# 7seg-2_54.net
KiCad netlist of a schematic drawn in EAGLE
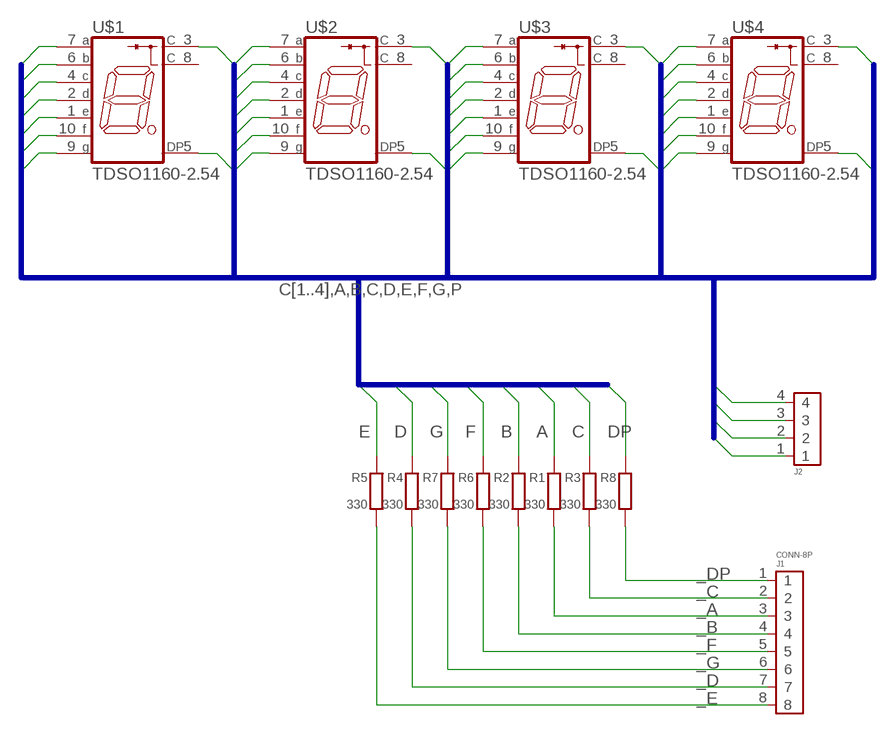
[diagram p0: schematic, sheet 1]

(export (version "E")
  (design (tool "Eeschema 10.0.6"))
  (components
    (comp (ref "J1")
      (value "CONN-8P")
      (footprint "eagle-import:CONN-8P")
      (libsource (lib "eagle-import") (part "CONN-8P"))
    )
    (comp (ref "J2")
      (value "CONN-4P-4P")
      (footprint "eagle-import:CONN-4P")
      (libsource (lib "eagle-import") (part "CONN-4P-4P"))
    )
    (comp (ref "R1")
      (value "330")
      (footprint "eagle-import:0202_5-V")
      (libsource (lib "eagle-import") (part "R0202/5-V"))
    )
    (comp (ref "R2")
      (value "330")
      (footprint "eagle-import:0202_5-V")
      (libsource (lib "eagle-import") (part "R0202/5-V"))
    )
    (comp (ref "R3")
      (value "330")
      (footprint "eagle-import:0202_5-V")
      (libsource (lib "eagle-import") (part "R0202/5-V"))
    )
    (comp (ref "R4")
      (value "330")
      (footprint "eagle-import:0202_5-V")
      (libsource (lib "eagle-import") (part "R0202/5-V"))
    )
    (comp (ref "R5")
      (value "330")
      (footprint "eagle-import:0202_5-V")
      (libsource (lib "eagle-import") (part "R0202/5-V"))
    )
    (comp (ref "R6")
      (value "330")
      (footprint "eagle-import:0202_5-V")
      (libsource (lib "eagle-import") (part "R0202/5-V"))
    )
    (comp (ref "R7")
      (value "330")
      (footprint "eagle-import:0202_5-V")
      (libsource (lib "eagle-import") (part "R0202/5-V"))
    )
    (comp (ref "R8")
      (value "330")
      (footprint "eagle-import:0202_5-V")
      (libsource (lib "eagle-import") (part "R0202/5-V"))
    )
    (comp (ref "U$1")
      (value "TDSO1160-2.54")
      (footprint "eagle-import:TDSX1150-2.54")
      (libsource (lib "eagle-import") (part "TDSO1160-2.54"))
    )
    (comp (ref "U$2")
      (value "TDSO1160-2.54")
      (footprint "eagle-import:TDSX1150-2.54")
      (libsource (lib "eagle-import") (part "TDSO1160-2.54"))
    )
    (comp (ref "U$3")
      (value "TDSO1160-2.54")
      (footprint "eagle-import:TDSX1150-2.54")
      (libsource (lib "eagle-import") (part "TDSO1160-2.54"))
    )
    (comp (ref "U$4")
      (value "TDSO1160-2.54")
      (footprint "eagle-import:TDSX1150-2.54")
      (libsource (lib "eagle-import") (part "TDSO1160-2.54"))
    )
  )
  (nets
    (net (code "2") (name "/A") (class "Default")
      (node (ref "R1") (pin "1") (pinfunction "2_1") (pintype "passive"))
      (node (ref "U$1") (pin "7") (pinfunction "A_7") (pintype "passive"))
      (node (ref "U$2") (pin "7") (pinfunction "A_7") (pintype "passive"))
      (node (ref "U$3") (pin "7") (pinfunction "A_7") (pintype "passive"))
      (node (ref "U$4") (pin "7") (pinfunction "A_7") (pintype "passive"))
    )
    (net (code "3") (name "/B") (class "Default")
      (node (ref "R2") (pin "1") (pinfunction "2_1") (pintype "passive"))
      (node (ref "U$1") (pin "6") (pinfunction "B_6") (pintype "passive"))
      (node (ref "U$2") (pin "6") (pinfunction "B_6") (pintype "passive"))
      (node (ref "U$3") (pin "6") (pinfunction "B_6") (pintype "passive"))
      (node (ref "U$4") (pin "6") (pinfunction "B_6") (pintype "passive"))
    )
    (net (code "4") (name "/C") (class "Default")
      (node (ref "R3") (pin "1") (pinfunction "2_1") (pintype "passive"))
      (node (ref "U$1") (pin "4") (pinfunction "C_4") (pintype "passive"))
      (node (ref "U$2") (pin "4") (pinfunction "C_4") (pintype "passive"))
      (node (ref "U$3") (pin "4") (pinfunction "C_4") (pintype "passive"))
      (node (ref "U$4") (pin "4") (pinfunction "C_4") (pintype "passive"))
    )
    (net (code "5") (name "/C1") (class "Default")
      (node (ref "J2") (pin "1") (pinfunction "1_1") (pintype "bidirectional"))
      (node (ref "U$1") (pin "3") (pinfunction "C_3") (pintype "passive"))
    )
    (net (code "6") (name "/C2") (class "Default")
      (node (ref "J2") (pin "2") (pinfunction "2_2") (pintype "bidirectional"))
      (node (ref "U$2") (pin "3") (pinfunction "C_3") (pintype "passive"))
    )
    (net (code "7") (name "/C3") (class "Default")
      (node (ref "J2") (pin "3") (pinfunction "3_3") (pintype "bidirectional"))
      (node (ref "U$3") (pin "3") (pinfunction "C_3") (pintype "passive"))
    )
    (net (code "8") (name "/C4") (class "Default")
      (node (ref "J2") (pin "4") (pinfunction "4_4") (pintype "bidirectional"))
      (node (ref "U$4") (pin "3") (pinfunction "C_3") (pintype "passive"))
    )
    (net (code "9") (name "/D") (class "Default")
      (node (ref "R4") (pin "1") (pinfunction "2_1") (pintype "passive"))
      (node (ref "U$1") (pin "2") (pinfunction "D_2") (pintype "passive"))
      (node (ref "U$2") (pin "2") (pinfunction "D_2") (pintype "passive"))
      (node (ref "U$3") (pin "2") (pinfunction "D_2") (pintype "passive"))
      (node (ref "U$4") (pin "2") (pinfunction "D_2") (pintype "passive"))
    )
    (net (code "10") (name "/DP") (class "Default")
      (node (ref "R8") (pin "1") (pinfunction "2_1") (pintype "passive"))
      (node (ref "U$1") (pin "5") (pinfunction "DP_5") (pintype "passive"))
      (node (ref "U$2") (pin "5") (pinfunction "DP_5") (pintype "passive"))
      (node (ref "U$3") (pin "5") (pinfunction "DP_5") (pintype "passive"))
      (node (ref "U$4") (pin "5") (pinfunction "DP_5") (pintype "passive"))
    )
    (net (code "11") (name "/E") (class "Default")
      (node (ref "R5") (pin "1") (pinfunction "2_1") (pintype "passive"))
      (node (ref "U$1") (pin "1") (pinfunction "E_1") (pintype "passive"))
      (node (ref "U$2") (pin "1") (pinfunction "E_1") (pintype "passive"))
      (node (ref "U$3") (pin "1") (pinfunction "E_1") (pintype "passive"))
      (node (ref "U$4") (pin "1") (pinfunction "E_1") (pintype "passive"))
    )
    (net (code "12") (name "/F") (class "Default")
      (node (ref "R6") (pin "1") (pinfunction "2_1") (pintype "passive"))
      (node (ref "U$1") (pin "10") (pinfunction "F_10") (pintype "passive"))
      (node (ref "U$2") (pin "10") (pinfunction "F_10") (pintype "passive"))
      (node (ref "U$3") (pin "10") (pinfunction "F_10") (pintype "passive"))
      (node (ref "U$4") (pin "10") (pinfunction "F_10") (pintype "passive"))
    )
    (net (code "13") (name "/G") (class "Default")
      (node (ref "R7") (pin "1") (pinfunction "2_1") (pintype "passive"))
      (node (ref "U$1") (pin "9") (pinfunction "G_9") (pintype "passive"))
      (node (ref "U$2") (pin "9") (pinfunction "G_9") (pintype "passive"))
      (node (ref "U$3") (pin "9") (pinfunction "G_9") (pintype "passive"))
      (node (ref "U$4") (pin "9") (pinfunction "G_9") (pintype "passive"))
    )
    (net (code "14") (name "/_A") (class "Default")
      (node (ref "J1") (pin "3") (pinfunction "3_3") (pintype "passive"))
      (node (ref "R1") (pin "2") (pinfunction "1_2") (pintype "passive"))
    )
    (net (code "15") (name "/_B") (class "Default")
      (node (ref "J1") (pin "4") (pinfunction "4_4") (pintype "passive"))
      (node (ref "R2") (pin "2") (pinfunction "1_2") (pintype "passive"))
    )
    (net (code "16") (name "/_C") (class "Default")
      (node (ref "J1") (pin "2") (pinfunction "2_2") (pintype "passive"))
      (node (ref "R3") (pin "2") (pinfunction "1_2") (pintype "passive"))
    )
    (net (code "17") (name "/_D") (class "Default")
      (node (ref "J1") (pin "7") (pinfunction "7_7") (pintype "passive"))
      (node (ref "R4") (pin "2") (pinfunction "1_2") (pintype "passive"))
    )
    (net (code "18") (name "/_DP") (class "Default")
      (node (ref "J1") (pin "1") (pinfunction "1_1") (pintype "passive"))
      (node (ref "R8") (pin "2") (pinfunction "1_2") (pintype "passive"))
    )
    (net (code "19") (name "/_E") (class "Default")
      (node (ref "J1") (pin "8") (pinfunction "8_8") (pintype "passive"))
      (node (ref "R5") (pin "2") (pinfunction "1_2") (pintype "passive"))
    )
    (net (code "20") (name "/_F") (class "Default")
      (node (ref "J1") (pin "5") (pinfunction "5_5") (pintype "passive"))
      (node (ref "R6") (pin "2") (pinfunction "1_2") (pintype "passive"))
    )
    (net (code "21") (name "/_G") (class "Default")
      (node (ref "J1") (pin "6") (pinfunction "6_6") (pintype "passive"))
      (node (ref "R7") (pin "2") (pinfunction "1_2") (pintype "passive"))
    )
    (net (code "23") (name "unconnected-(U$1-C-Pad8)") (class "Default")
      (node (ref "U$1") (pin "8") (pinfunction "C_8") (pintype "passive"))
    )
    (net (code "24") (name "unconnected-(U$2-C-Pad8)") (class "Default")
      (node (ref "U$2") (pin "8") (pinfunction "C_8") (pintype "passive"))
    )
    (net (code "25") (name "unconnected-(U$3-C-Pad8)") (class "Default")
      (node (ref "U$3") (pin "8") (pinfunction "C_8") (pintype "passive"))
    )
    (net (code "26") (name "unconnected-(U$4-C-Pad8)") (class "Default")
      (node (ref "U$4") (pin "8") (pinfunction "C_8") (pintype "passive"))
    )
  )
)
